# STM32_schemtic.net
KiCad netlist of a schematic drawn in Altium Designer
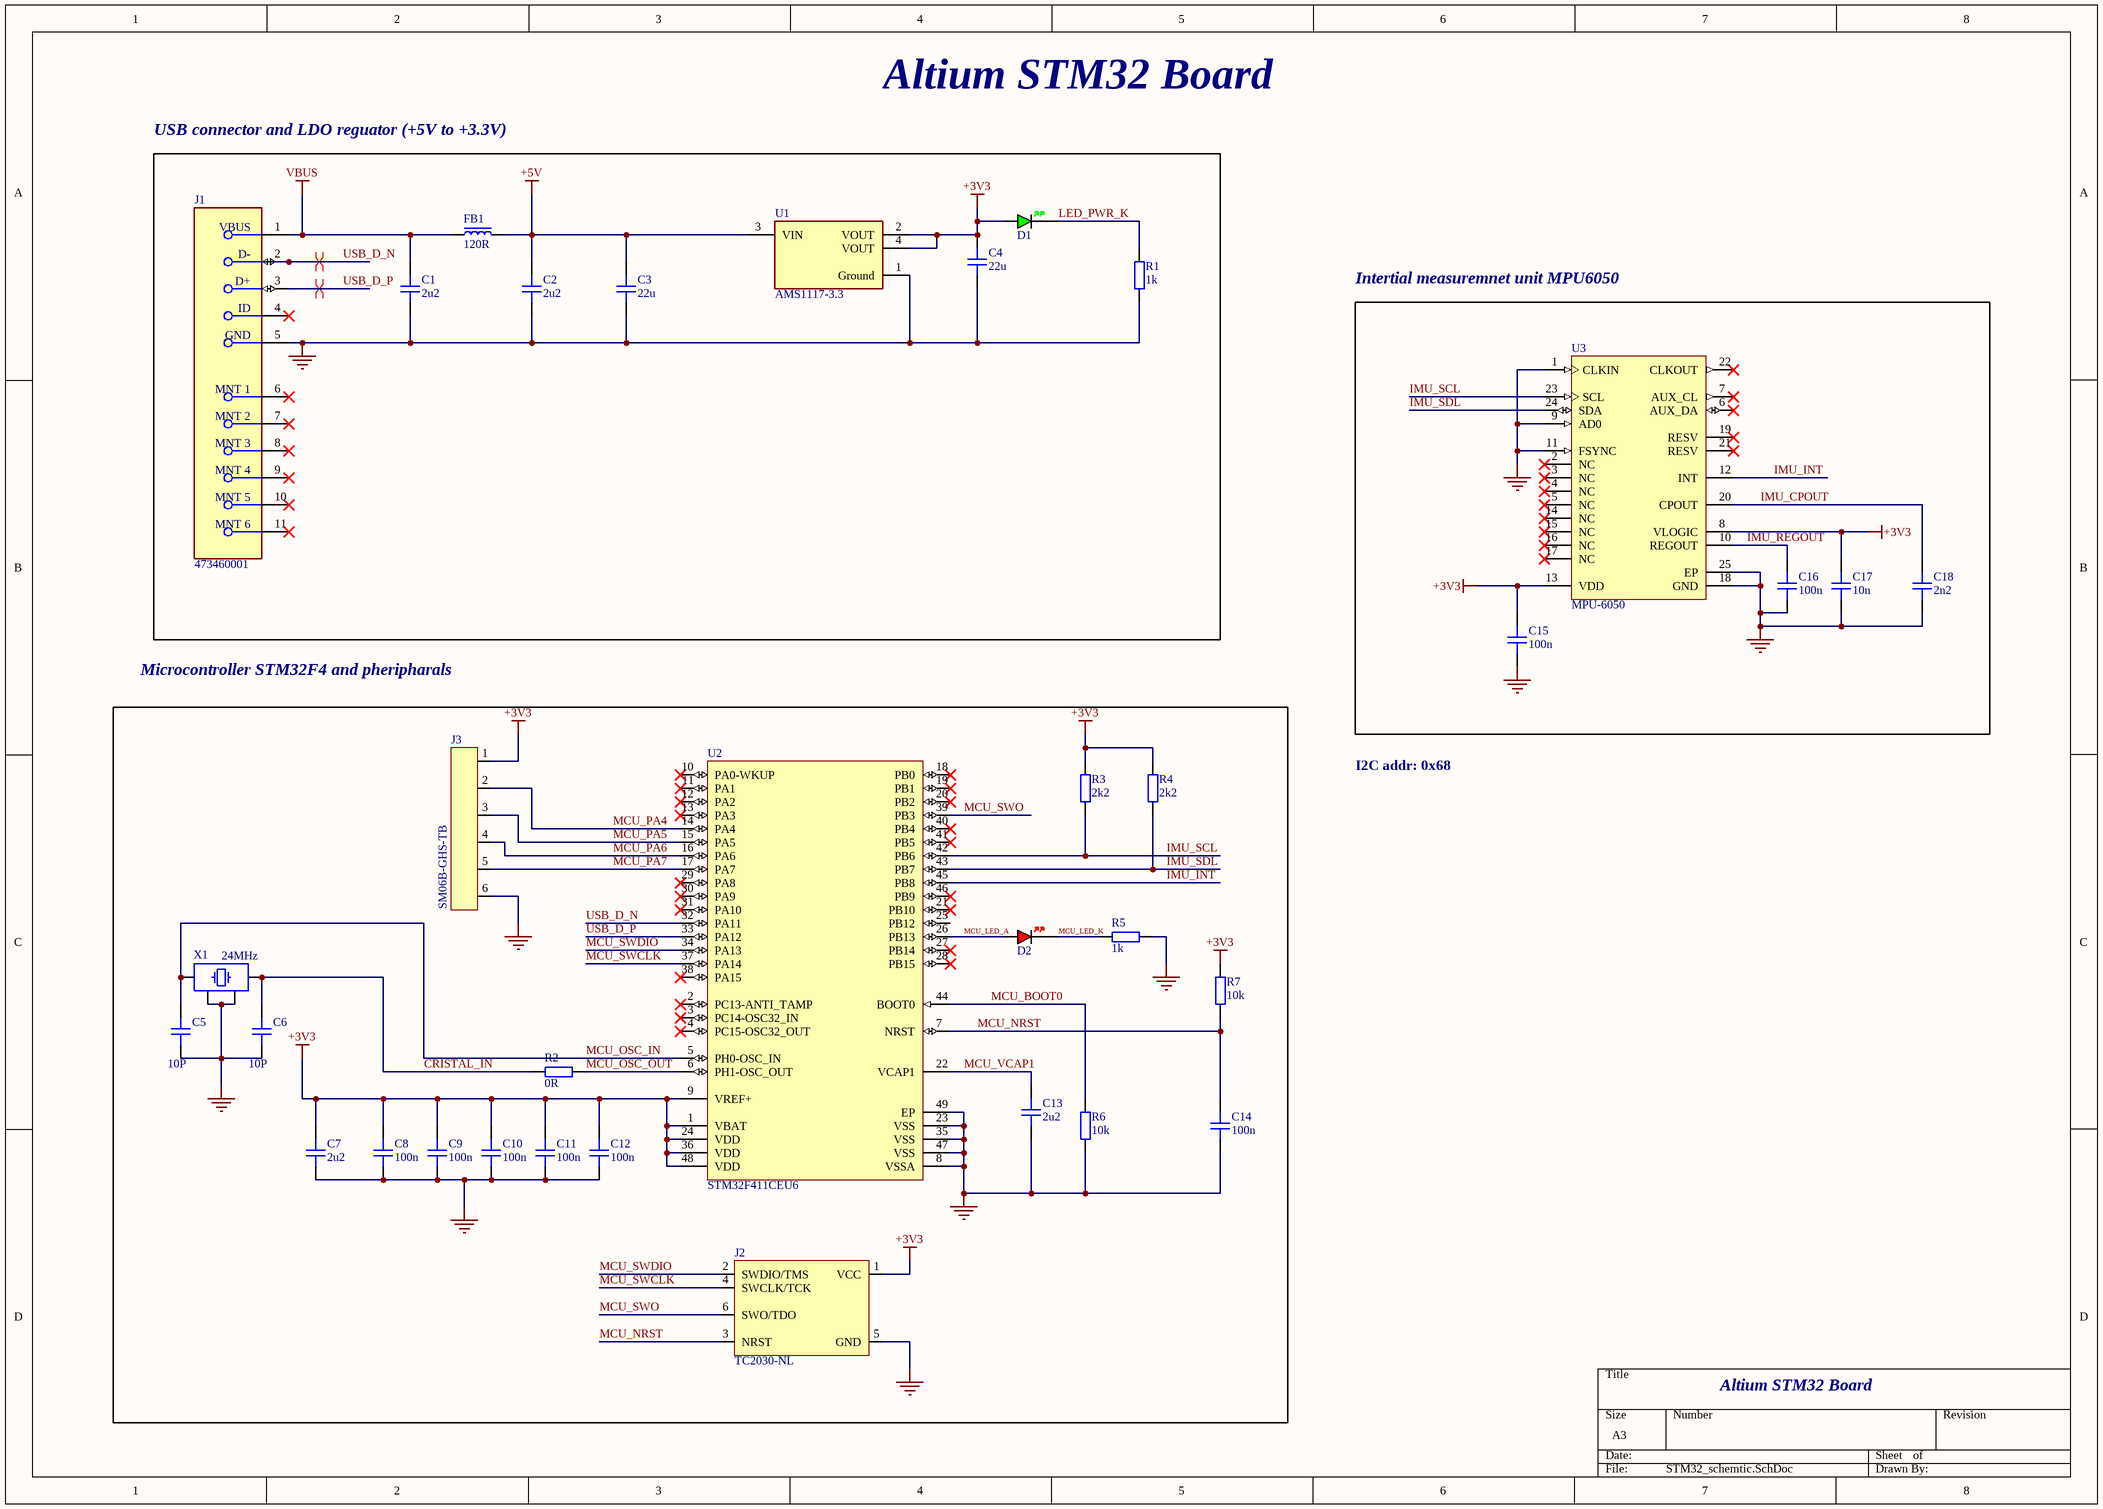
[diagram p0: STM32_schemtic.SchDoc]

(export (version "E")
  (design (tool "Eeschema 10.0.6"))
  (components
    (comp (ref "C1")
      (value "2u2")
      (footprint "CAP_0603")
      (description "Capacitor SMD 0603")
      (libsource (lib "Schematic-Lib-PhilsLab") (part "CAP_0603"))
    )
    (comp (ref "C2")
      (value "2u2")
      (footprint "CAP_0603")
      (description "Capacitor SMD 0603")
      (libsource (lib "Schematic-Lib-PhilsLab") (part "CAP_0603"))
    )
    (comp (ref "C3")
      (value "22u")
      (footprint "CAP_0805")
      (description "Capacitor SMD 0805")
      (libsource (lib "Schematic-Lib-PhilsLab") (part "CAP_0805"))
    )
    (comp (ref "C4")
      (value "22u")
      (footprint "CAP_0805")
      (description "Capacitor SMD 0805")
      (libsource (lib "Schematic-Lib-PhilsLab") (part "CAP_0805"))
    )
    (comp (ref "C5")
      (value "10P")
      (footprint "CAP_0402")
      (description "Capacitor SMD 0402")
      (libsource (lib "Schematic-Lib-PhilsLab") (part "CAP_0402"))
    )
    (comp (ref "C6")
      (value "10P")
      (footprint "CAP_0402")
      (description "Capacitor SMD 0402")
      (libsource (lib "Schematic-Lib-PhilsLab") (part "CAP_0402"))
    )
    (comp (ref "C7")
      (value "2u2")
      (footprint "CAP_0603")
      (description "Capacitor SMD 0603")
      (libsource (lib "Schematic-Lib-PhilsLab") (part "CAP_0603"))
    )
    (comp (ref "C8")
      (value "100n")
      (footprint "CAP_0402")
      (description "Capacitor SMD 0402")
      (libsource (lib "Schematic-Lib-PhilsLab") (part "CAP_0402"))
    )
    (comp (ref "C9")
      (value "100n")
      (footprint "CAP_0402")
      (description "Capacitor SMD 0402")
      (libsource (lib "Schematic-Lib-PhilsLab") (part "CAP_0402"))
    )
    (comp (ref "C10")
      (value "100n")
      (footprint "CAP_0402")
      (description "Capacitor SMD 0402")
      (libsource (lib "Schematic-Lib-PhilsLab") (part "CAP_0402"))
    )
    (comp (ref "C11")
      (value "100n")
      (footprint "CAP_0402")
      (description "Capacitor SMD 0402")
      (libsource (lib "Schematic-Lib-PhilsLab") (part "CAP_0402"))
    )
    (comp (ref "C12")
      (value "100n")
      (footprint "CAP_0402")
      (description "Capacitor SMD 0402")
      (libsource (lib "Schematic-Lib-PhilsLab") (part "CAP_0402"))
    )
    (comp (ref "C13")
      (value "2u2")
      (footprint "CAP_0603")
      (description "Capacitor SMD 0603")
      (libsource (lib "Schematic-Lib-PhilsLab") (part "CAP_0603"))
    )
    (comp (ref "C14")
      (value "100n")
      (footprint "CAP_0402")
      (description "Capacitor SMD 0402")
      (libsource (lib "Schematic-Lib-PhilsLab") (part "CAP_0402"))
    )
    (comp (ref "C15")
      (value "100n")
      (footprint "CAP_0402")
      (description "Capacitor SMD 0402")
      (libsource (lib "Schematic-Lib-PhilsLab") (part "CAP_0402"))
    )
    (comp (ref "C16")
      (value "100n")
      (footprint "CAP_0402")
      (description "Capacitor SMD 0402")
      (libsource (lib "Schematic-Lib-PhilsLab") (part "CAP_0402"))
    )
    (comp (ref "C17")
      (value "10n")
      (footprint "CAP_0402")
      (description "Capacitor SMD 0402")
      (libsource (lib "Schematic-Lib-PhilsLab") (part "CAP_0402"))
    )
    (comp (ref "C18")
      (value "2n2")
      (footprint "CAP_0402")
      (description "Capacitor SMD 0402")
      (libsource (lib "Schematic-Lib-PhilsLab") (part "CAP_0402"))
    )
    (comp (ref "D1")
      (value "GREEN")
      (footprint "LED_0402_GREEN")
      (description "LED 0402 GREEN SMD")
      (libsource (lib "Schematic-Lib-PhilsLab") (part "LED_0402_GREEN"))
    )
    (comp (ref "D2")
      (value "RED")
      (footprint "LED_0402_RED")
      (description "LED 0402 RED SMD")
      (libsource (lib "Schematic-Lib-PhilsLab") (part "LED_0402_RED"))
    )
    (comp (ref "FB1")
      (value "120R")
      (footprint "FB_0603")
      (description "Ferrite Bead SMD 0603")
      (libsource (lib "Schematic-Lib-PhilsLab") (part "FB_0603"))
    )
    (comp (ref "J1")
      (value "473460001")
      (footprint "FP-473460001-MFG")
      (description "CONN RCPT USB2.0 MICRO B SMD R/A")
      (fields
        (field (name "OCTOPART") "https://octopart.com/47346-0001-molex-7164928")
        (field (name "MANUFACTURER") "Molex")
      )
      (libsource (lib "Altium Content Vault") (part "53ae1f1d9b557310b43ca686e5bb76a"))
    )
    (comp (ref "J2")
      (value "TC2030-NL")
      (footprint "TC2030-NL-FP")
      (description "Tag-Connect No-Solder SWD Debug Connector (No Legs) DO NOT PLACE")
      (fields
        (field (name "MANUFACTURER") "Tag-Connect")
        (field (name "MANUFACTURER PART NUMBER") "TC2030-NL-FP")
      )
      (libsource (lib "Schematic-Lib-PhilsLab") (part "TC2030-NL"))
    )
    (comp (ref "J3")
      (value "SM06B-GHS-TB")
      (footprint "SM06B-GHS-TB")
      (description "Header Connector 6 Position 1.25MM Pitch SMD Horizontal JST GH")
      (fields (field (name "MANUFACTURER") "JST"))
      (libsource (lib "Schematic-Lib-PhilsLab") (part "SM06B-GHS-TB"))
    )
    (comp (ref "R1")
      (value "1k")
      (footprint "RES_0402")
      (description "Resistor SMD 0402")
      (libsource (lib "Schematic-Lib-PhilsLab") (part "RES_0402"))
    )
    (comp (ref "R2")
      (value "0R")
      (footprint "RES_0402")
      (description "Resistor SMD 0402")
      (libsource (lib "Schematic-Lib-PhilsLab") (part "RES_0402"))
    )
    (comp (ref "R3")
      (value "2k2")
      (footprint "RES_0402")
      (description "Resistor SMD 0402")
      (libsource (lib "Schematic-Lib-PhilsLab") (part "RES_0402"))
    )
    (comp (ref "R4")
      (value "2k2")
      (footprint "RES_0402")
      (description "Resistor SMD 0402")
      (libsource (lib "Schematic-Lib-PhilsLab") (part "RES_0402"))
    )
    (comp (ref "R5")
      (value "1k")
      (footprint "RES_0402")
      (description "Resistor SMD 0402")
      (libsource (lib "Schematic-Lib-PhilsLab") (part "RES_0402"))
    )
    (comp (ref "R6")
      (value "10k")
      (footprint "RES_0402")
      (description "Resistor SMD 0402")
      (libsource (lib "Schematic-Lib-PhilsLab") (part "RES_0402"))
    )
    (comp (ref "R7")
      (value "10k")
      (footprint "RES_0402")
      (description "Resistor SMD 0402")
      (libsource (lib "Schematic-Lib-PhilsLab") (part "RES_0402"))
    )
    (comp (ref "U1")
      (value "AMS1117-3.3")
      (footprint "FP-AMS1117-IPC_C")
      (description "LDO Voltage Regulators 1A, 3.3V")
      (fields
        (field (name "OCTOPART") "https://octopart.com/ams1117-3.3-advanced+monolithic+systems-25899300")
        (field (name "MANUFACTURER") "Advanced Monolithic Systems")
      )
      (libsource (lib "Altium Content Vault") (part "8bdbb5f8e77002000e30dd2845d0354"))
    )
    (comp (ref "U2")
      (value "STM32F411CEU6")
      (footprint "STM-UFQFPN48_L")
      (libsource (lib "Altium Content Vault") (part "MC-ARM-STM32F411-UFQFPN48"))
    )
    (comp (ref "U3")
      (value "MPU-6050")
      (footprint "IS-QFN-24_V")
      (fields (field (name "MANUFACTURER") "InvenSense"))
      (libsource (lib "Altium Content Vault") (part "IS-MPU-6050-QFN-24"))
    )
    (comp (ref "X1")
      (value "24MHz")
      (footprint "XTAL_3225")
      (description "Crystal SMD 24MHz 10PPM 7pF 3225")
      (fields
        (field (name "MANUFACTURER") "Epson")
        (field (name "MANUFACTURER PART NUMBER") "TSX-3225 24.0000MF15X-AC")
      )
      (libsource (lib "Schematic-Lib-PhilsLab") (part "TSX-3225_24.0000MF15X-AC"))
    )
  )
  (nets
    (net (code "1") (name "+3V3") (class "Default")
      (node (ref "C10") (pin "2") (pinfunction "2_2") (pintype "passive"))
      (node (ref "C11") (pin "2") (pinfunction "2_2") (pintype "passive"))
      (node (ref "C12") (pin "2") (pinfunction "2_2") (pintype "passive"))
      (node (ref "C15") (pin "2") (pinfunction "2_2") (pintype "passive"))
      (node (ref "C17") (pin "2") (pinfunction "2_2") (pintype "passive"))
      (node (ref "C4") (pin "2") (pinfunction "2_2") (pintype "passive"))
      (node (ref "C7") (pin "2") (pinfunction "2_2") (pintype "passive"))
      (node (ref "C8") (pin "2") (pinfunction "2_2") (pintype "passive"))
      (node (ref "C9") (pin "2") (pinfunction "2_2") (pintype "passive"))
      (node (ref "D1") (pin "A") (pinfunction "A_A") (pintype "passive"))
      (node (ref "J2") (pin "1") (pinfunction "VCC_1") (pintype "passive"))
      (node (ref "J3") (pin "1") (pinfunction "1_1") (pintype "passive"))
      (node (ref "R3") (pin "2") (pinfunction "2_2") (pintype "passive"))
      (node (ref "R4") (pin "2") (pinfunction "2_2") (pintype "passive"))
      (node (ref "R7") (pin "2") (pinfunction "2_2") (pintype "passive"))
      (node (ref "U1") (pin "2") (pinfunction "VOUT_2") (pintype "passive"))
      (node (ref "U1") (pin "4") (pinfunction "VOUT_4") (pintype "passive"))
      (node (ref "U2") (pin "1") (pinfunction "VBAT_1") (pintype "power_in"))
      (node (ref "U2") (pin "24") (pinfunction "VDD_24") (pintype "power_in"))
      (node (ref "U2") (pin "36") (pinfunction "VDD_36") (pintype "power_in"))
      (node (ref "U2") (pin "48") (pinfunction "VDD_48") (pintype "power_in"))
      (node (ref "U2") (pin "9") (pinfunction "VREF+_9") (pintype "power_in"))
      (node (ref "U3") (pin "13") (pinfunction "VDD_13") (pintype "power_in"))
      (node (ref "U3") (pin "8") (pinfunction "VLOGIC_8") (pintype "power_in"))
    )
    (net (code "2") (name "+5V") (class "Default")
      (node (ref "C2") (pin "2") (pinfunction "2_2") (pintype "passive"))
      (node (ref "C3") (pin "2") (pinfunction "2_2") (pintype "passive"))
      (node (ref "FB1") (pin "2") (pinfunction "2_2") (pintype "passive"))
      (node (ref "U1") (pin "3") (pinfunction "VIN_3") (pintype "power_in"))
    )
    (net (code "3") (name "/CRISTAL_IN") (class "Default")
      (node (ref "C6") (pin "1") (pinfunction "1_1") (pintype "passive"))
      (node (ref "R2") (pin "1") (pinfunction "1_1") (pintype "passive"))
      (node (ref "X1") (pin "3") (pinfunction "3_3") (pintype "passive"))
    )
    (net (code "4") (name "/IMU_CPOUT") (class "Default")
      (node (ref "C18") (pin "2") (pinfunction "2_2") (pintype "passive"))
      (node (ref "U3") (pin "20") (pinfunction "CPOUT_20") (pintype "passive"))
    )
    (net (code "5") (name "/IMU_INT") (class "Default")
      (node (ref "U2") (pin "45") (pinfunction "PB8_45") (pintype "bidirectional"))
      (node (ref "U3") (pin "12") (pinfunction "INT_12") (pintype "open_collector"))
    )
    (net (code "6") (name "/IMU_REGOUT") (class "Default")
      (node (ref "C16") (pin "2") (pinfunction "2_2") (pintype "passive"))
      (node (ref "U3") (pin "10") (pinfunction "REGOUT_10") (pintype "passive"))
    )
    (net (code "7") (name "/IMU_SCL") (class "Default")
      (node (ref "R3") (pin "1") (pinfunction "1_1") (pintype "passive"))
      (node (ref "U2") (pin "42") (pinfunction "PB6_42") (pintype "bidirectional"))
      (node (ref "U3") (pin "23") (pinfunction "SCL_23") (pintype "input"))
    )
    (net (code "8") (name "/IMU_SDL") (class "Default")
      (node (ref "R4") (pin "1") (pinfunction "1_1") (pintype "passive"))
      (node (ref "U2") (pin "43") (pinfunction "PB7_43") (pintype "bidirectional"))
      (node (ref "U3") (pin "24") (pinfunction "SDA_24") (pintype "bidirectional"))
    )
    (net (code "9") (name "/LED_PWR_K") (class "Default")
      (node (ref "D1") (pin "K") (pinfunction "K_K") (pintype "passive"))
      (node (ref "R1") (pin "1") (pinfunction "1_1") (pintype "passive"))
    )
    (net (code "10") (name "/MCU_BOOT0") (class "Default")
      (node (ref "R6") (pin "2") (pinfunction "2_2") (pintype "passive"))
      (node (ref "U2") (pin "44") (pinfunction "BOOT0_44") (pintype "input"))
    )
    (net (code "11") (name "/MCU_LED_A") (class "Default")
      (node (ref "D2") (pin "A") (pinfunction "A_A") (pintype "passive"))
      (node (ref "U2") (pin "26") (pinfunction "PB13_26") (pintype "bidirectional"))
    )
    (net (code "12") (name "/MCU_LED_K") (class "Default")
      (node (ref "D2") (pin "K") (pinfunction "K_K") (pintype "passive"))
      (node (ref "R5") (pin "1") (pinfunction "1_1") (pintype "passive"))
    )
    (net (code "13") (name "/MCU_NRST") (class "Default")
      (node (ref "C14") (pin "2") (pinfunction "2_2") (pintype "passive"))
      (node (ref "J2") (pin "3") (pinfunction "NRST_3") (pintype "passive"))
      (node (ref "R7") (pin "1") (pinfunction "1_1") (pintype "passive"))
      (node (ref "U2") (pin "7") (pinfunction "NRST_7") (pintype "bidirectional"))
    )
    (net (code "14") (name "/MCU_OSC_IN") (class "Default")
      (node (ref "C5") (pin "1") (pinfunction "1_1") (pintype "passive"))
      (node (ref "U2") (pin "5") (pinfunction "PH0-OSC_IN_5") (pintype "bidirectional"))
      (node (ref "X1") (pin "1") (pinfunction "1_1") (pintype "passive"))
    )
    (net (code "15") (name "/MCU_OSC_OUT") (class "Default")
      (node (ref "R2") (pin "2") (pinfunction "2_2") (pintype "passive"))
      (node (ref "U2") (pin "6") (pinfunction "PH1-OSC_OUT_6") (pintype "bidirectional"))
    )
    (net (code "16") (name "/MCU_PA4") (class "Default")
      (node (ref "J3") (pin "2") (pinfunction "2_2") (pintype "passive"))
      (node (ref "U2") (pin "14") (pinfunction "PA4_14") (pintype "bidirectional"))
    )
    (net (code "17") (name "/MCU_PA5") (class "Default")
      (node (ref "J3") (pin "3") (pinfunction "3_3") (pintype "passive"))
      (node (ref "U2") (pin "15") (pinfunction "PA5_15") (pintype "bidirectional"))
    )
    (net (code "18") (name "/MCU_PA6") (class "Default")
      (node (ref "J3") (pin "4") (pinfunction "4_4") (pintype "passive"))
      (node (ref "U2") (pin "16") (pinfunction "PA6_16") (pintype "bidirectional"))
    )
    (net (code "19") (name "/MCU_PA7") (class "Default")
      (node (ref "J3") (pin "5") (pinfunction "5_5") (pintype "passive"))
      (node (ref "U2") (pin "17") (pinfunction "PA7_17") (pintype "bidirectional"))
    )
    (net (code "20") (name "/MCU_SWCLK") (class "Default")
      (node (ref "J2") (pin "4") (pinfunction "SWCLK/TCK_4") (pintype "passive"))
      (node (ref "U2") (pin "37") (pinfunction "PA14_37") (pintype "bidirectional"))
    )
    (net (code "21") (name "/MCU_SWDIO") (class "Default")
      (node (ref "J2") (pin "2") (pinfunction "SWDIO/TMS_2") (pintype "passive"))
      (node (ref "U2") (pin "34") (pinfunction "PA13_34") (pintype "bidirectional"))
    )
    (net (code "22") (name "/MCU_SWO") (class "Default")
      (node (ref "J2") (pin "6") (pinfunction "SWO/TDO_6") (pintype "passive"))
      (node (ref "U2") (pin "39") (pinfunction "PB3_39") (pintype "bidirectional"))
    )
    (net (code "23") (name "/MCU_VCAP1") (class "Default")
      (node (ref "C13") (pin "2") (pinfunction "2_2") (pintype "passive"))
      (node (ref "U2") (pin "22") (pinfunction "VCAP1_22") (pintype "passive"))
    )
    (net (code "24") (name "/USB_D_N") (class "Default")
      (node (ref "J1") (pin "2") (pinfunction "D-_2") (pintype "bidirectional"))
      (node (ref "U2") (pin "32") (pinfunction "PA11_32") (pintype "bidirectional"))
    )
    (net (code "25") (name "/USB_D_P") (class "Default")
      (node (ref "J1") (pin "3") (pinfunction "D+_3") (pintype "bidirectional"))
      (node (ref "U2") (pin "33") (pinfunction "PA12_33") (pintype "bidirectional"))
    )
    (net (code "26") (name "GND") (class "Default")
      (node (ref "C1") (pin "1") (pinfunction "1_1") (pintype "passive"))
      (node (ref "C10") (pin "1") (pinfunction "1_1") (pintype "passive"))
      (node (ref "C11") (pin "1") (pinfunction "1_1") (pintype "passive"))
      (node (ref "C12") (pin "1") (pinfunction "1_1") (pintype "passive"))
      (node (ref "C13") (pin "1") (pinfunction "1_1") (pintype "passive"))
      (node (ref "C14") (pin "1") (pinfunction "1_1") (pintype "passive"))
      (node (ref "C15") (pin "1") (pinfunction "1_1") (pintype "passive"))
      (node (ref "C16") (pin "1") (pinfunction "1_1") (pintype "passive"))
      (node (ref "C17") (pin "1") (pinfunction "1_1") (pintype "passive"))
      (node (ref "C18") (pin "1") (pinfunction "1_1") (pintype "passive"))
      (node (ref "C2") (pin "1") (pinfunction "1_1") (pintype "passive"))
      (node (ref "C3") (pin "1") (pinfunction "1_1") (pintype "passive"))
      (node (ref "C4") (pin "1") (pinfunction "1_1") (pintype "passive"))
      (node (ref "C5") (pin "2") (pinfunction "2_2") (pintype "passive"))
      (node (ref "C6") (pin "2") (pinfunction "2_2") (pintype "passive"))
      (node (ref "C7") (pin "1") (pinfunction "1_1") (pintype "passive"))
      (node (ref "C8") (pin "1") (pinfunction "1_1") (pintype "passive"))
      (node (ref "C9") (pin "1") (pinfunction "1_1") (pintype "passive"))
      (node (ref "J1") (pin "5") (pinfunction "GND_5") (pintype "power_in"))
      (node (ref "J2") (pin "5") (pinfunction "GND_5") (pintype "passive"))
      (node (ref "J3") (pin "6") (pinfunction "6_6") (pintype "passive"))
      (node (ref "R1") (pin "2") (pinfunction "2_2") (pintype "passive"))
      (node (ref "R5") (pin "2") (pinfunction "2_2") (pintype "passive"))
      (node (ref "R6") (pin "1") (pinfunction "1_1") (pintype "passive"))
      (node (ref "U1") (pin "1") (pinfunction "Ground_1") (pintype "power_in"))
      (node (ref "U2") (pin "23") (pinfunction "VSS_23") (pintype "power_in"))
      (node (ref "U2") (pin "35") (pinfunction "VSS_35") (pintype "power_in"))
      (node (ref "U2") (pin "47") (pinfunction "VSS_47") (pintype "power_in"))
      (node (ref "U2") (pin "49") (pinfunction "EP_49") (pintype "power_in"))
      (node (ref "U2") (pin "8") (pinfunction "VSSA_8") (pintype "power_in"))
      (node (ref "U3") (pin "1") (pinfunction "CLKIN_1") (pintype "input"))
      (node (ref "U3") (pin "11") (pinfunction "FSYNC_11") (pintype "input"))
      (node (ref "U3") (pin "18") (pinfunction "GND_18") (pintype "power_in"))
      (node (ref "U3") (pin "25") (pinfunction "EP_25") (pintype "power_in"))
      (node (ref "U3") (pin "9") (pinfunction "AD0_9") (pintype "input"))
      (node (ref "X1") (pin "2") (pinfunction "2_2") (pintype "passive"))
      (node (ref "X1") (pin "4") (pinfunction "4_4") (pintype "passive"))
    )
    (net (code "27") (name "VBUS") (class "Default")
      (node (ref "C1") (pin "2") (pinfunction "2_2") (pintype "passive"))
      (node (ref "FB1") (pin "1") (pinfunction "1_1") (pintype "passive"))
      (node (ref "J1") (pin "1") (pinfunction "VBUS_1") (pintype "power_in"))
    )
    (net (code "28") (name "unconnected-(J1-ID-Pad4)") (class "Default")
      (node (ref "J1") (pin "4") (pinfunction "ID_4") (pintype "passive+no_connect"))
    )
    (net (code "29") (name "unconnected-(J1-MNT_1-Pad6)") (class "Default")
      (node (ref "J1") (pin "6") (pinfunction "MNT_1_6") (pintype "passive+no_connect"))
    )
    (net (code "30") (name "unconnected-(J1-MNT_2-Pad7)") (class "Default")
      (node (ref "J1") (pin "7") (pinfunction "MNT_2_7") (pintype "passive+no_connect"))
    )
    (net (code "31") (name "unconnected-(J1-MNT_3-Pad8)") (class "Default")
      (node (ref "J1") (pin "8") (pinfunction "MNT_3_8") (pintype "passive+no_connect"))
    )
    (net (code "32") (name "unconnected-(J1-MNT_4-Pad9)") (class "Default")
      (node (ref "J1") (pin "9") (pinfunction "MNT_4_9") (pintype "passive+no_connect"))
    )
    (net (code "33") (name "unconnected-(J1-MNT_5-Pad10)") (class "Default")
      (node (ref "J1") (pin "10") (pinfunction "MNT_5_10") (pintype "passive+no_connect"))
    )
    (net (code "34") (name "unconnected-(J1-MNT_6-Pad11)") (class "Default")
      (node (ref "J1") (pin "11") (pinfunction "MNT_6_11") (pintype "passive+no_connect"))
    )
    (net (code "35") (name "unconnected-(U2-PA0-WKUP-Pad10)") (class "Default")
      (node (ref "U2") (pin "10") (pinfunction "PA0-WKUP_10") (pintype "bidirectional+no_connect"))
    )
    (net (code "36") (name "unconnected-(U2-PA1-Pad11)") (class "Default")
      (node (ref "U2") (pin "11") (pinfunction "PA1_11") (pintype "bidirectional+no_connect"))
    )
    (net (code "37") (name "unconnected-(U2-PA2-Pad12)") (class "Default")
      (node (ref "U2") (pin "12") (pinfunction "PA2_12") (pintype "bidirectional+no_connect"))
    )
    (net (code "38") (name "unconnected-(U2-PA3-Pad13)") (class "Default")
      (node (ref "U2") (pin "13") (pinfunction "PA3_13") (pintype "bidirectional+no_connect"))
    )
    (net (code "39") (name "unconnected-(U2-PA8-Pad29)") (class "Default")
      (node (ref "U2") (pin "29") (pinfunction "PA8_29") (pintype "bidirectional+no_connect"))
    )
    (net (code "40") (name "unconnected-(U2-PA9-Pad30)") (class "Default")
      (node (ref "U2") (pin "30") (pinfunction "PA9_30") (pintype "bidirectional+no_connect"))
    )
    (net (code "41") (name "unconnected-(U2-PA10-Pad31)") (class "Default")
      (node (ref "U2") (pin "31") (pinfunction "PA10_31") (pintype "bidirectional+no_connect"))
    )
    (net (code "42") (name "unconnected-(U2-PA15-Pad38)") (class "Default")
      (node (ref "U2") (pin "38") (pinfunction "PA15_38") (pintype "bidirectional+no_connect"))
    )
    (net (code "43") (name "unconnected-(U2-PB0-Pad18)") (class "Default")
      (node (ref "U2") (pin "18") (pinfunction "PB0_18") (pintype "bidirectional+no_connect"))
    )
    (net (code "44") (name "unconnected-(U2-PB1-Pad19)") (class "Default")
      (node (ref "U2") (pin "19") (pinfunction "PB1_19") (pintype "bidirectional+no_connect"))
    )
    (net (code "45") (name "unconnected-(U2-PB2-Pad20)") (class "Default")
      (node (ref "U2") (pin "20") (pinfunction "PB2_20") (pintype "bidirectional+no_connect"))
    )
    (net (code "46") (name "unconnected-(U2-PB4-Pad40)") (class "Default")
      (node (ref "U2") (pin "40") (pinfunction "PB4_40") (pintype "bidirectional+no_connect"))
    )
    (net (code "47") (name "unconnected-(U2-PB5-Pad41)") (class "Default")
      (node (ref "U2") (pin "41") (pinfunction "PB5_41") (pintype "bidirectional+no_connect"))
    )
    (net (code "48") (name "unconnected-(U2-PB9-Pad46)") (class "Default")
      (node (ref "U2") (pin "46") (pinfunction "PB9_46") (pintype "bidirectional+no_connect"))
    )
    (net (code "49") (name "unconnected-(U2-PB10-Pad21)") (class "Default")
      (node (ref "U2") (pin "21") (pinfunction "PB10_21") (pintype "bidirectional+no_connect"))
    )
    (net (code "50") (name "unconnected-(U2-PB12-Pad25)") (class "Default")
      (node (ref "U2") (pin "25") (pinfunction "PB12_25") (pintype "bidirectional"))
    )
    (net (code "51") (name "unconnected-(U2-PB14-Pad27)") (class "Default")
      (node (ref "U2") (pin "27") (pinfunction "PB14_27") (pintype "bidirectional+no_connect"))
    )
    (net (code "52") (name "unconnected-(U2-PB15-Pad28)") (class "Default")
      (node (ref "U2") (pin "28") (pinfunction "PB15_28") (pintype "bidirectional+no_connect"))
    )
    (net (code "53") (name "unconnected-(U2-PC13-ANTI_TAMP-Pad2)") (class "Default")
      (node (ref "U2") (pin "2") (pinfunction "PC13-ANTI_TAMP_2") (pintype "bidirectional+no_connect"))
    )
    (net (code "54") (name "unconnected-(U2-PC14-OSC32_IN-Pad3)") (class "Default")
      (node (ref "U2") (pin "3") (pinfunction "PC14-OSC32_IN_3") (pintype "bidirectional+no_connect"))
    )
    (net (code "55") (name "unconnected-(U2-PC15-OSC32_OUT-Pad4)") (class "Default")
      (node (ref "U2") (pin "4") (pinfunction "PC15-OSC32_OUT_4") (pintype "bidirectional+no_connect"))
    )
    (net (code "56") (name "unconnected-(U3-AUX_CL-Pad7)") (class "Default")
      (node (ref "U3") (pin "7") (pinfunction "AUX_CL_7") (pintype "output+no_connect"))
    )
    (net (code "57") (name "unconnected-(U3-AUX_DA-Pad6)") (class "Default")
      (node (ref "U3") (pin "6") (pinfunction "AUX_DA_6") (pintype "bidirectional+no_connect"))
    )
    (net (code "58") (name "unconnected-(U3-CLKOUT-Pad22)") (class "Default")
      (node (ref "U3") (pin "22") (pinfunction "CLKOUT_22") (pintype "output+no_connect"))
    )
    (net (code "59") (name "unconnected-(U3-NC-Pad2)") (class "Default")
      (node (ref "U3") (pin "2") (pinfunction "NC_2") (pintype "passive+no_connect"))
    )
    (net (code "60") (name "unconnected-(U3-NC-Pad3)") (class "Default")
      (node (ref "U3") (pin "3") (pinfunction "NC_3") (pintype "passive+no_connect"))
    )
    (net (code "61") (name "unconnected-(U3-NC-Pad4)") (class "Default")
      (node (ref "U3") (pin "4") (pinfunction "NC_4") (pintype "passive+no_connect"))
    )
    (net (code "62") (name "unconnected-(U3-NC-Pad5)") (class "Default")
      (node (ref "U3") (pin "5") (pinfunction "NC_5") (pintype "passive+no_connect"))
    )
    (net (code "63") (name "unconnected-(U3-NC-Pad14)") (class "Default")
      (node (ref "U3") (pin "14") (pinfunction "NC_14") (pintype "passive+no_connect"))
    )
    (net (code "64") (name "unconnected-(U3-NC-Pad15)") (class "Default")
      (node (ref "U3") (pin "15") (pinfunction "NC_15") (pintype "passive+no_connect"))
    )
    (net (code "65") (name "unconnected-(U3-NC-Pad16)") (class "Default")
      (node (ref "U3") (pin "16") (pinfunction "NC_16") (pintype "passive+no_connect"))
    )
    (net (code "66") (name "unconnected-(U3-NC-Pad17)") (class "Default")
      (node (ref "U3") (pin "17") (pinfunction "NC_17") (pintype "passive+no_connect"))
    )
    (net (code "67") (name "unconnected-(U3-RESV-Pad19)") (class "Default")
      (node (ref "U3") (pin "19") (pinfunction "RESV_19") (pintype "passive+no_connect"))
    )
    (net (code "68") (name "unconnected-(U3-RESV-Pad21)") (class "Default")
      (node (ref "U3") (pin "21") (pinfunction "RESV_21") (pintype "passive+no_connect"))
    )
  )
)
